# decawave-power.net
KiCad netlist of a schematic drawn in Altium Designer
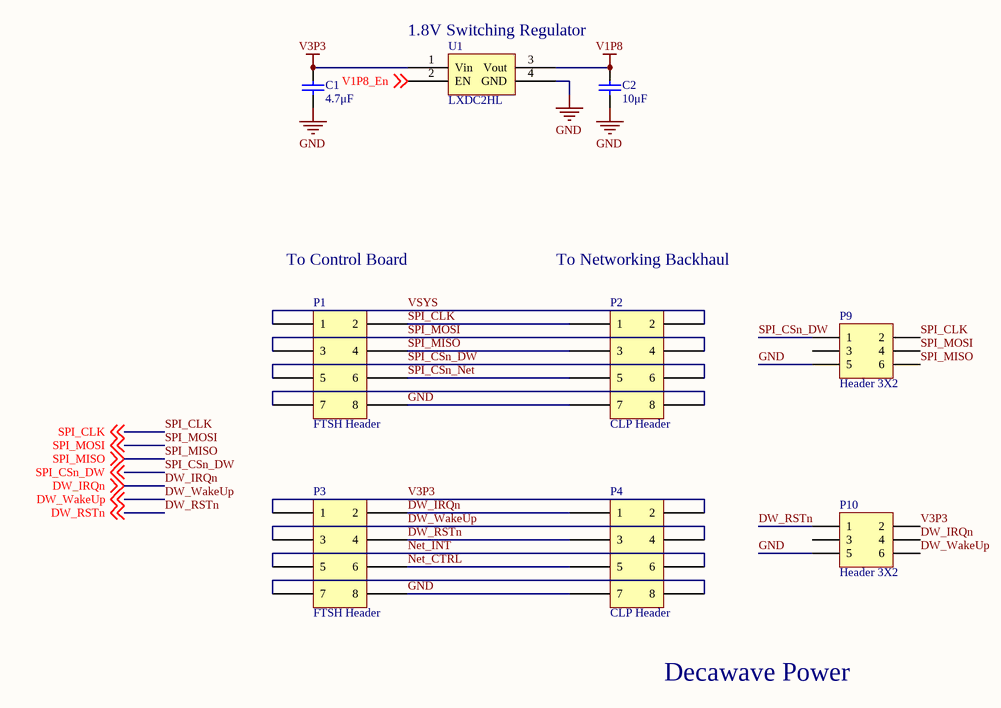
[diagram p0: decawave-power.SchDoc]

(export (version "E")
  (design (tool "Eeschema 10.0.6"))
  (components
    (comp (ref "C1")
      (value "4.7μF")
      (footprint "0603")
      (description "Capacitor (Semiconductor SIM Model)")
      (fields
        (field (name "DISTPARTNO") "587-1441-1-ND")
        (field (name "MANPARTNO") "LMK107BJ475KA-T")
        (field (name "PUBLISHER") "Altium Limited")
      )
      (libsource (lib "decawave-lib") (part "Cap Chip"))
    )
    (comp (ref "C2")
      (value "10μF")
      (footprint "0603")
      (description "Capacitor (Semiconductor SIM Model)")
      (fields
        (field (name "DISTPARTNO") "587-3412-1-ND")
        (field (name "MANPARTNO") "LMK107BBJ106MAHT")
        (field (name "PUBLISHER") "Altium Limited")
      )
      (libsource (lib "decawave-lib") (part "Cap Chip"))
    )
    (comp (ref "P1")
      (value "FTSH Header")
      (footprint "SAM_FTSH_2_4")
      (description "Samtec FTSH 2x4 0.05\" Male Header")
      (libsource (lib "decawave-lib") (part "FTSH Header"))
    )
    (comp (ref "P2")
      (value "CLP Header")
      (footprint "SAM_CLP_2_4")
      (description "Samtec CLP 2x4 0.05\" Female Header")
      (libsource (lib "decawave-lib") (part "CLP Header"))
    )
    (comp (ref "P3")
      (value "FTSH Header")
      (footprint "SAM_FTSH_2_4")
      (description "Samtec FTSH 2x4 0.05\" Male Header")
      (libsource (lib "decawave-lib") (part "FTSH Header"))
    )
    (comp (ref "P4")
      (value "CLP Header")
      (footprint "SAM_CLP_2_4")
      (description "Samtec CLP 2x4 0.05\" Female Header")
      (libsource (lib "decawave-lib") (part "CLP Header"))
    )
    (comp (ref "P9")
      (value "Header 3X2")
      (footprint "HDR2X3")
      (description "Header, 3-Pin, Dual row")
      (fields (field (name "PUBLISHER") "Altium Limited"))
      (libsource (lib "Miscellaneous Connectors") (part "Header 3X2"))
    )
    (comp (ref "P10")
      (value "Header 3X2")
      (footprint "HDR2X3")
      (description "Header, 3-Pin, Dual row")
      (fields (field (name "PUBLISHER") "Altium Limited"))
      (libsource (lib "Miscellaneous Connectors") (part "Header 3X2"))
    )
    (comp (ref "U1")
      (value "LXDC2HL")
      (footprint "LXDC2HL")
      (fields (field (name "DISTPARTNO") "490-5791-1-ND") (field (name "MANPARTNO") "LXDC2HL18A-052"))
      (libsource (lib "decawave-lib") (part "LXDC2HL"))
    )
  )
  (nets
    (net (code "1") (name "/Net_CTRL") (class "Default")
      (node (ref "P3") (pin "6") (pinfunction "6_6") (pintype "passive"))
      (node (ref "P4") (pin "5") (pinfunction "5_5") (pintype "passive"))
    )
    (net (code "2") (name "/Net_INT") (class "Default")
      (node (ref "P3") (pin "5") (pinfunction "5_5") (pintype "passive"))
      (node (ref "P4") (pin "6") (pinfunction "6_6") (pintype "passive"))
    )
    (net (code "3") (name "/SPI_CSn_Net") (class "Default")
      (node (ref "P1") (pin "6") (pinfunction "6_6") (pintype "passive"))
      (node (ref "P2") (pin "5") (pinfunction "5_5") (pintype "passive"))
    )
    (net (code "4") (name "/VSYS") (class "Default")
      (node (ref "P1") (pin "1") (pinfunction "1_1") (pintype "passive"))
      (node (ref "P2") (pin "2") (pinfunction "2_2") (pintype "passive"))
    )
    (net (code "5") (name "DW_IRQn") (class "Default")
      (node (ref "P10") (pin "4") (pinfunction "4_4") (pintype "passive"))
      (node (ref "P3") (pin "2") (pinfunction "2_2") (pintype "passive"))
      (node (ref "P4") (pin "1") (pinfunction "1_1") (pintype "passive"))
    )
    (net (code "6") (name "DW_RSTn") (class "Default")
      (node (ref "P10") (pin "1") (pinfunction "1_1") (pintype "passive"))
      (node (ref "P3") (pin "4") (pinfunction "4_4") (pintype "passive"))
      (node (ref "P4") (pin "3") (pinfunction "3_3") (pintype "passive"))
    )
    (net (code "7") (name "DW_WakeUp") (class "Default")
      (node (ref "P10") (pin "6") (pinfunction "6_6") (pintype "passive"))
      (node (ref "P3") (pin "3") (pinfunction "3_3") (pintype "passive"))
      (node (ref "P4") (pin "4") (pinfunction "4_4") (pintype "passive"))
    )
    (net (code "8") (name "GND") (class "Default")
      (node (ref "C1") (pin "2") (pinfunction "2_2") (pintype "passive"))
      (node (ref "C2") (pin "2") (pinfunction "2_2") (pintype "passive"))
      (node (ref "P1") (pin "8") (pinfunction "8_8") (pintype "passive"))
      (node (ref "P10") (pin "5") (pinfunction "5_5") (pintype "passive"))
      (node (ref "P2") (pin "7") (pinfunction "7_7") (pintype "passive"))
      (node (ref "P3") (pin "8") (pinfunction "8_8") (pintype "passive"))
      (node (ref "P4") (pin "7") (pinfunction "7_7") (pintype "passive"))
      (node (ref "P9") (pin "5") (pinfunction "5_5") (pintype "passive"))
      (node (ref "U1") (pin "4") (pinfunction "GND_4") (pintype "passive"))
    )
    (net (code "9") (name "Net-(P1-Pad7)") (class "Default")
      (node (ref "P1") (pin "7") (pinfunction "7_7") (pintype "passive"))
      (node (ref "P2") (pin "8") (pinfunction "8_8") (pintype "passive"))
    )
    (net (code "10") (name "Net-(P3-Pad7)") (class "Default")
      (node (ref "P3") (pin "7") (pinfunction "7_7") (pintype "passive"))
      (node (ref "P4") (pin "8") (pinfunction "8_8") (pintype "passive"))
    )
    (net (code "11") (name "SPI_CLK") (class "Default")
      (node (ref "P1") (pin "2") (pinfunction "2_2") (pintype "passive"))
      (node (ref "P2") (pin "1") (pinfunction "1_1") (pintype "passive"))
      (node (ref "P9") (pin "2") (pinfunction "2_2") (pintype "passive"))
    )
    (net (code "12") (name "SPI_CSn_DW") (class "Default")
      (node (ref "P1") (pin "5") (pinfunction "5_5") (pintype "passive"))
      (node (ref "P2") (pin "6") (pinfunction "6_6") (pintype "passive"))
      (node (ref "P9") (pin "1") (pinfunction "1_1") (pintype "passive"))
    )
    (net (code "13") (name "SPI_MISO") (class "Default")
      (node (ref "P1") (pin "4") (pinfunction "4_4") (pintype "passive"))
      (node (ref "P2") (pin "3") (pinfunction "3_3") (pintype "passive"))
      (node (ref "P9") (pin "6") (pinfunction "6_6") (pintype "passive"))
    )
    (net (code "14") (name "SPI_MOSI") (class "Default")
      (node (ref "P1") (pin "3") (pinfunction "3_3") (pintype "passive"))
      (node (ref "P2") (pin "4") (pinfunction "4_4") (pintype "passive"))
      (node (ref "P9") (pin "4") (pinfunction "4_4") (pintype "passive"))
    )
    (net (code "15") (name "V1P8") (class "Default")
      (node (ref "C2") (pin "1") (pinfunction "1_1") (pintype "passive"))
      (node (ref "U1") (pin "3") (pinfunction "Vout_3") (pintype "passive"))
    )
    (net (code "16") (name "V1P8_En") (class "Default")
      (node (ref "U1") (pin "2") (pinfunction "EN_2") (pintype "passive"))
    )
    (net (code "17") (name "V3P3") (class "Default")
      (node (ref "C1") (pin "1") (pinfunction "1_1") (pintype "passive"))
      (node (ref "P10") (pin "2") (pinfunction "2_2") (pintype "passive"))
      (node (ref "P3") (pin "1") (pinfunction "1_1") (pintype "passive"))
      (node (ref "P4") (pin "2") (pinfunction "2_2") (pintype "passive"))
      (node (ref "U1") (pin "1") (pinfunction "Vin_1") (pintype "passive"))
    )
    (net (code "18") (name "unconnected-(P9-Pad3)") (class "Default")
      (node (ref "P9") (pin "3") (pinfunction "3_3") (pintype "passive"))
    )
    (net (code "19") (name "unconnected-(P10-Pad3)") (class "Default")
      (node (ref "P10") (pin "3") (pinfunction "3_3") (pintype "passive"))
    )
  )
)
